# Refill_device.net
KiCad netlist of a schematic drawn in EAGLE
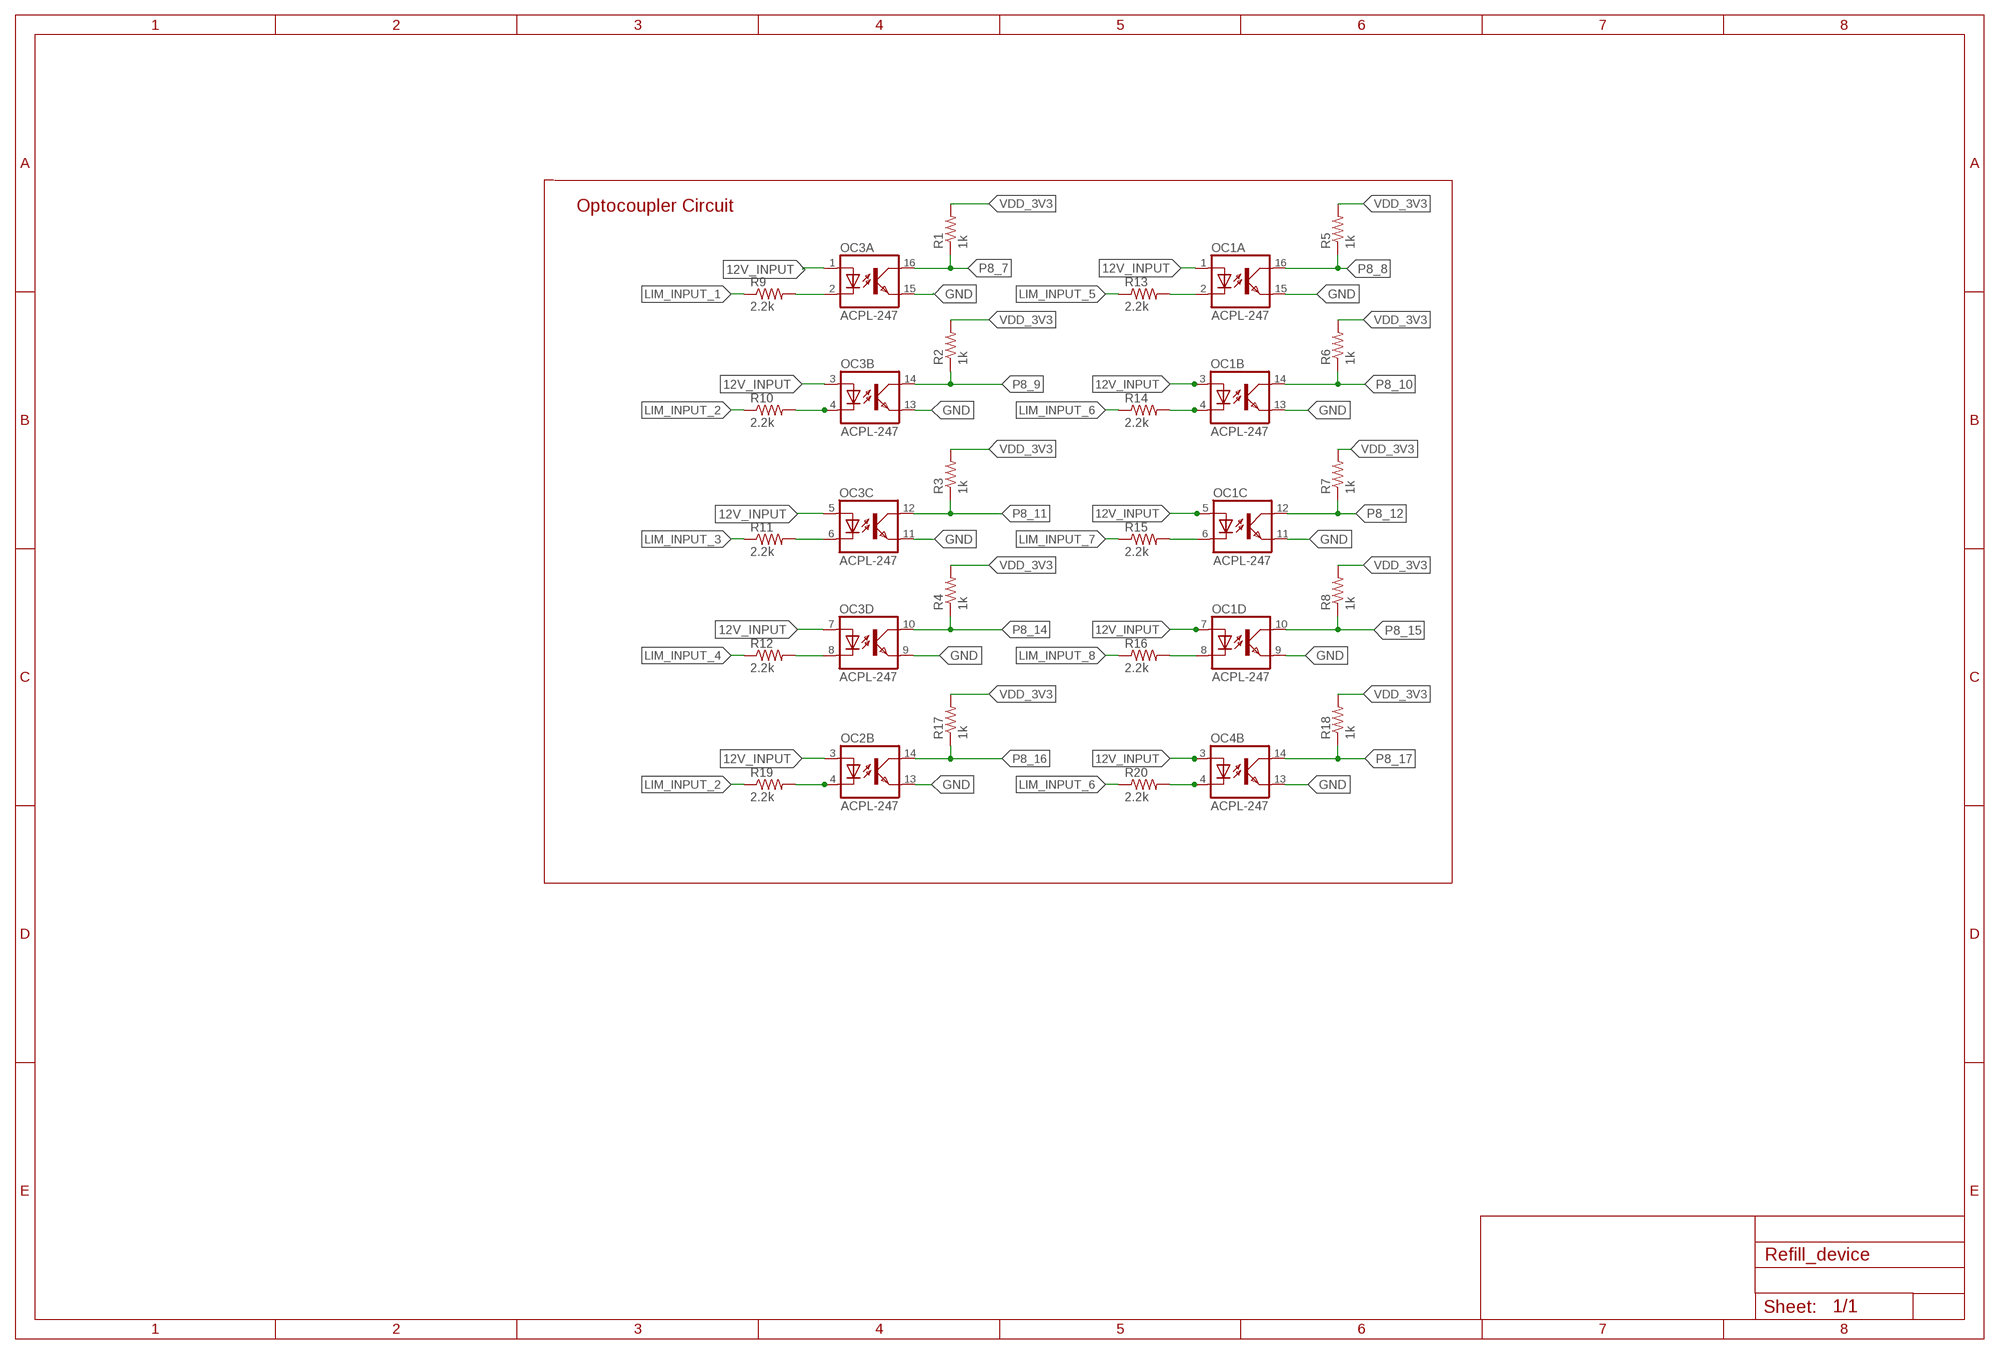
[diagram p0: schematic, sheet 1]

(export (version "E")
  (design (tool "Eeschema 10.0.6"))
  (components
    (comp (ref "OC1")
      (value "ACPL-247")
      (footprint "eagle-import:SOP16")
      (libsource (lib "eagle-import") (part "ACPL-247"))
    )
    (comp (ref "OC2")
      (value "ACPL-247")
      (footprint "eagle-import:SOP16")
      (libsource (lib "eagle-import") (part "ACPL-247"))
    )
    (comp (ref "OC3")
      (value "ACPL-247")
      (footprint "eagle-import:SOP16")
      (libsource (lib "eagle-import") (part "ACPL-247"))
    )
    (comp (ref "OC4")
      (value "ACPL-247")
      (footprint "eagle-import:SOP16")
      (libsource (lib "eagle-import") (part "ACPL-247"))
    )
    (comp (ref "R1")
      (value "1k")
      (footprint "eagle-import:R0603")
      (libsource (lib "eagle-import") (part "R-US_R0603"))
    )
    (comp (ref "R2")
      (value "1k")
      (footprint "eagle-import:R0603")
      (libsource (lib "eagle-import") (part "R-US_R0603"))
    )
    (comp (ref "R3")
      (value "1k")
      (footprint "eagle-import:R0603")
      (libsource (lib "eagle-import") (part "R-US_R0603"))
    )
    (comp (ref "R4")
      (value "1k")
      (footprint "eagle-import:R0603")
      (libsource (lib "eagle-import") (part "R-US_R0603"))
    )
    (comp (ref "R5")
      (value "1k")
      (footprint "eagle-import:R0603")
      (libsource (lib "eagle-import") (part "R-US_R0603"))
    )
    (comp (ref "R6")
      (value "1k")
      (footprint "eagle-import:R0603")
      (libsource (lib "eagle-import") (part "R-US_R0603"))
    )
    (comp (ref "R7")
      (value "1k")
      (footprint "eagle-import:R0603")
      (libsource (lib "eagle-import") (part "R-US_R0603"))
    )
    (comp (ref "R8")
      (value "1k")
      (footprint "eagle-import:R0603")
      (libsource (lib "eagle-import") (part "R-US_R0603"))
    )
    (comp (ref "R9")
      (value "2.2k")
      (footprint "eagle-import:R0603")
      (libsource (lib "eagle-import") (part "R-US_R0603"))
    )
    (comp (ref "R10")
      (value "2.2k")
      (footprint "eagle-import:R0603")
      (libsource (lib "eagle-import") (part "R-US_R0603"))
    )
    (comp (ref "R11")
      (value "2.2k")
      (footprint "eagle-import:R0603")
      (libsource (lib "eagle-import") (part "R-US_R0603"))
    )
    (comp (ref "R12")
      (value "2.2k")
      (footprint "eagle-import:R0603")
      (libsource (lib "eagle-import") (part "R-US_R0603"))
    )
    (comp (ref "R13")
      (value "2.2k")
      (footprint "eagle-import:R0603")
      (libsource (lib "eagle-import") (part "R-US_R0603"))
    )
    (comp (ref "R14")
      (value "2.2k")
      (footprint "eagle-import:R0603")
      (libsource (lib "eagle-import") (part "R-US_R0603"))
    )
    (comp (ref "R15")
      (value "2.2k")
      (footprint "eagle-import:R0603")
      (libsource (lib "eagle-import") (part "R-US_R0603"))
    )
    (comp (ref "R16")
      (value "2.2k")
      (footprint "eagle-import:R0603")
      (libsource (lib "eagle-import") (part "R-US_R0603"))
    )
    (comp (ref "R17")
      (value "1k")
      (footprint "eagle-import:R0603")
      (libsource (lib "eagle-import") (part "R-US_R0603"))
    )
    (comp (ref "R18")
      (value "1k")
      (footprint "eagle-import:R0603")
      (libsource (lib "eagle-import") (part "R-US_R0603"))
    )
    (comp (ref "R19")
      (value "2.2k")
      (footprint "eagle-import:R0603")
      (libsource (lib "eagle-import") (part "R-US_R0603"))
    )
    (comp (ref "R20")
      (value "2.2k")
      (footprint "eagle-import:R0603")
      (libsource (lib "eagle-import") (part "R-US_R0603"))
    )
  )
  (nets
    (net (code "1") (name "12V_INPUT") (class "Default")
      (node (ref "OC1") (pin "1") (pinfunction "A_1") (pintype "passive"))
      (node (ref "OC1") (pin "3") (pinfunction "A_3") (pintype "passive"))
      (node (ref "OC1") (pin "5") (pinfunction "A_5") (pintype "passive"))
      (node (ref "OC1") (pin "7") (pinfunction "A_7") (pintype "passive"))
      (node (ref "OC2") (pin "3") (pinfunction "A_3") (pintype "passive"))
      (node (ref "OC3") (pin "1") (pinfunction "A_1") (pintype "passive"))
      (node (ref "OC3") (pin "3") (pinfunction "A_3") (pintype "passive"))
      (node (ref "OC3") (pin "5") (pinfunction "A_5") (pintype "passive"))
      (node (ref "OC3") (pin "7") (pinfunction "A_7") (pintype "passive"))
      (node (ref "OC4") (pin "3") (pinfunction "A_3") (pintype "passive"))
    )
    (net (code "2") (name "GND") (class "Default")
      (node (ref "OC1") (pin "11") (pinfunction "EMIT_11") (pintype "passive"))
      (node (ref "OC1") (pin "13") (pinfunction "EMIT_13") (pintype "passive"))
      (node (ref "OC1") (pin "15") (pinfunction "EMIT_15") (pintype "passive"))
      (node (ref "OC1") (pin "9") (pinfunction "EMIT_9") (pintype "passive"))
      (node (ref "OC2") (pin "13") (pinfunction "EMIT_13") (pintype "passive"))
      (node (ref "OC3") (pin "11") (pinfunction "EMIT_11") (pintype "passive"))
      (node (ref "OC3") (pin "13") (pinfunction "EMIT_13") (pintype "passive"))
      (node (ref "OC3") (pin "15") (pinfunction "EMIT_15") (pintype "passive"))
      (node (ref "OC3") (pin "9") (pinfunction "EMIT_9") (pintype "passive"))
      (node (ref "OC4") (pin "13") (pinfunction "EMIT_13") (pintype "passive"))
    )
    (net (code "3") (name "LIM_INPUT_1") (class "Default")
      (node (ref "R9") (pin "1") (pinfunction "1_1") (pintype "passive"))
    )
    (net (code "4") (name "LIM_INPUT_2") (class "Default")
      (node (ref "R10") (pin "1") (pinfunction "1_1") (pintype "passive"))
      (node (ref "R19") (pin "1") (pinfunction "1_1") (pintype "passive"))
    )
    (net (code "5") (name "LIM_INPUT_3") (class "Default")
      (node (ref "R11") (pin "1") (pinfunction "1_1") (pintype "passive"))
    )
    (net (code "6") (name "LIM_INPUT_4") (class "Default")
      (node (ref "R12") (pin "1") (pinfunction "1_1") (pintype "passive"))
    )
    (net (code "7") (name "LIM_INPUT_5") (class "Default")
      (node (ref "R13") (pin "1") (pinfunction "1_1") (pintype "passive"))
    )
    (net (code "8") (name "LIM_INPUT_6") (class "Default")
      (node (ref "R14") (pin "1") (pinfunction "1_1") (pintype "passive"))
      (node (ref "R20") (pin "1") (pinfunction "1_1") (pintype "passive"))
    )
    (net (code "9") (name "LIM_INPUT_7") (class "Default")
      (node (ref "R15") (pin "1") (pinfunction "1_1") (pintype "passive"))
    )
    (net (code "10") (name "LIM_INPUT_8") (class "Default")
      (node (ref "R16") (pin "1") (pinfunction "1_1") (pintype "passive"))
    )
    (net (code "11") (name "Net-(OC1A-C)") (class "Default")
      (node (ref "OC1") (pin "2") (pinfunction "C_2") (pintype "passive"))
      (node (ref "R13") (pin "2") (pinfunction "2_2") (pintype "passive"))
    )
    (net (code "12") (name "Net-(OC1B-C)") (class "Default")
      (node (ref "OC1") (pin "4") (pinfunction "C_4") (pintype "passive"))
      (node (ref "R14") (pin "2") (pinfunction "2_2") (pintype "passive"))
    )
    (net (code "13") (name "Net-(OC1C-C)") (class "Default")
      (node (ref "OC1") (pin "6") (pinfunction "C_6") (pintype "passive"))
      (node (ref "R15") (pin "2") (pinfunction "2_2") (pintype "passive"))
    )
    (net (code "14") (name "Net-(OC1D-C)") (class "Default")
      (node (ref "OC1") (pin "8") (pinfunction "C_8") (pintype "passive"))
      (node (ref "R16") (pin "2") (pinfunction "2_2") (pintype "passive"))
    )
    (net (code "15") (name "Net-(OC2B-C)") (class "Default")
      (node (ref "OC2") (pin "4") (pinfunction "C_4") (pintype "passive"))
      (node (ref "R19") (pin "2") (pinfunction "2_2") (pintype "passive"))
    )
    (net (code "16") (name "Net-(OC3A-C)") (class "Default")
      (node (ref "OC3") (pin "2") (pinfunction "C_2") (pintype "passive"))
      (node (ref "R9") (pin "2") (pinfunction "2_2") (pintype "passive"))
    )
    (net (code "17") (name "Net-(OC3B-C)") (class "Default")
      (node (ref "OC3") (pin "4") (pinfunction "C_4") (pintype "passive"))
      (node (ref "R10") (pin "2") (pinfunction "2_2") (pintype "passive"))
    )
    (net (code "18") (name "Net-(OC3C-C)") (class "Default")
      (node (ref "OC3") (pin "6") (pinfunction "C_6") (pintype "passive"))
      (node (ref "R11") (pin "2") (pinfunction "2_2") (pintype "passive"))
    )
    (net (code "19") (name "Net-(OC3D-C)") (class "Default")
      (node (ref "OC3") (pin "8") (pinfunction "C_8") (pintype "passive"))
      (node (ref "R12") (pin "2") (pinfunction "2_2") (pintype "passive"))
    )
    (net (code "20") (name "Net-(OC4B-C)") (class "Default")
      (node (ref "OC4") (pin "4") (pinfunction "C_4") (pintype "passive"))
      (node (ref "R20") (pin "2") (pinfunction "2_2") (pintype "passive"))
    )
    (net (code "21") (name "P8_7") (class "Default")
      (node (ref "OC3") (pin "16") (pinfunction "COL_16") (pintype "passive"))
      (node (ref "R1") (pin "1") (pinfunction "1_1") (pintype "passive"))
    )
    (net (code "22") (name "P8_8") (class "Default")
      (node (ref "OC1") (pin "16") (pinfunction "COL_16") (pintype "passive"))
      (node (ref "R5") (pin "1") (pinfunction "1_1") (pintype "passive"))
    )
    (net (code "23") (name "P8_9") (class "Default")
      (node (ref "OC3") (pin "14") (pinfunction "COL_14") (pintype "passive"))
      (node (ref "R2") (pin "1") (pinfunction "1_1") (pintype "passive"))
    )
    (net (code "24") (name "P8_10") (class "Default")
      (node (ref "OC1") (pin "14") (pinfunction "COL_14") (pintype "passive"))
      (node (ref "R6") (pin "1") (pinfunction "1_1") (pintype "passive"))
    )
    (net (code "25") (name "P8_11") (class "Default")
      (node (ref "OC3") (pin "12") (pinfunction "COL_12") (pintype "passive"))
      (node (ref "R3") (pin "1") (pinfunction "1_1") (pintype "passive"))
    )
    (net (code "26") (name "P8_12") (class "Default")
      (node (ref "OC1") (pin "12") (pinfunction "COL_12") (pintype "passive"))
      (node (ref "R7") (pin "1") (pinfunction "1_1") (pintype "passive"))
    )
    (net (code "27") (name "P8_14") (class "Default")
      (node (ref "OC3") (pin "10") (pinfunction "COL_10") (pintype "passive"))
      (node (ref "R4") (pin "1") (pinfunction "1_1") (pintype "passive"))
    )
    (net (code "28") (name "P8_15") (class "Default")
      (node (ref "OC1") (pin "10") (pinfunction "COL_10") (pintype "passive"))
      (node (ref "R8") (pin "1") (pinfunction "1_1") (pintype "passive"))
    )
    (net (code "29") (name "P8_16") (class "Default")
      (node (ref "OC2") (pin "14") (pinfunction "COL_14") (pintype "passive"))
      (node (ref "R17") (pin "1") (pinfunction "1_1") (pintype "passive"))
    )
    (net (code "30") (name "P8_17") (class "Default")
      (node (ref "OC4") (pin "14") (pinfunction "COL_14") (pintype "passive"))
      (node (ref "R18") (pin "1") (pinfunction "1_1") (pintype "passive"))
    )
    (net (code "31") (name "VDD_3V3") (class "Default")
      (node (ref "R1") (pin "2") (pinfunction "2_2") (pintype "passive"))
      (node (ref "R17") (pin "2") (pinfunction "2_2") (pintype "passive"))
      (node (ref "R18") (pin "2") (pinfunction "2_2") (pintype "passive"))
      (node (ref "R2") (pin "2") (pinfunction "2_2") (pintype "passive"))
      (node (ref "R3") (pin "2") (pinfunction "2_2") (pintype "passive"))
      (node (ref "R4") (pin "2") (pinfunction "2_2") (pintype "passive"))
      (node (ref "R5") (pin "2") (pinfunction "2_2") (pintype "passive"))
      (node (ref "R6") (pin "2") (pinfunction "2_2") (pintype "passive"))
      (node (ref "R7") (pin "2") (pinfunction "2_2") (pintype "passive"))
      (node (ref "R8") (pin "2") (pinfunction "2_2") (pintype "passive"))
    )
  )
)
